# cooler.net
KiCad netlist of a schematic drawn in EAGLE
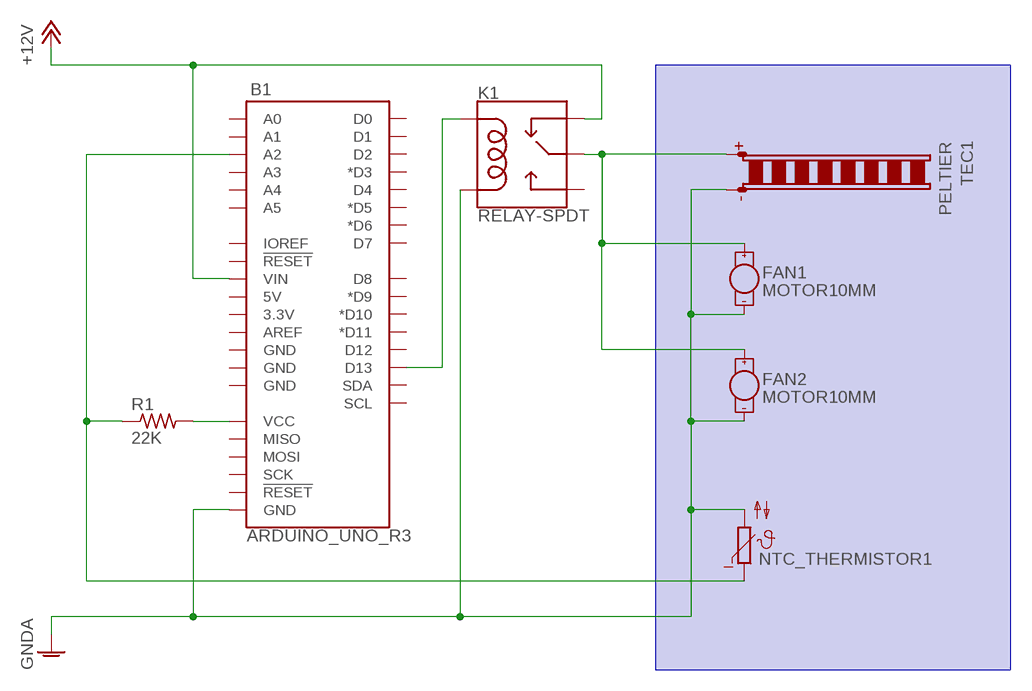
[diagram p0: schematic, sheet 1]

(export (version "E")
  (design (tool "Eeschema 10.0.6"))
  (components
    (comp (ref "B1")
      (value "ARDUINO_UNO_R3")
      (footprint "eagle-import:ARDUINO_R3")
      (libsource (lib "eagle-import") (part "ARDUINO_UNO_R3"))
    )
    (comp (ref "FAN1")
      (value "MOTOR10MM")
      (footprint "eagle-import:VIBE-MOTOR-10MM")
      (libsource (lib "eagle-import") (part "MOTOR10MM"))
    )
    (comp (ref "FAN2")
      (value "MOTOR10MM")
      (footprint "eagle-import:VIBE-MOTOR-10MM")
      (libsource (lib "eagle-import") (part "MOTOR10MM"))
    )
    (comp (ref "K1")
      (value "RELAY-SPDT")
      (footprint "eagle-import:RELAY_G5LE")
      (libsource (lib "eagle-import") (part "RELAY-SPDT"))
    )
    (comp (ref "NTC_THERMISTOR1")
      (value "B57164")
      (footprint "eagle-import:B57164")
      (fields (field (name "MPN") "B57164K474K52"))
      (libsource (lib "eagle-import") (part "B57164"))
    )
    (comp (ref "R1")
      (value "22K")
      (footprint "eagle-import:0204_5")
      (libsource (lib "eagle-import") (part "R-US_0204/5"))
    )
    (comp (ref "TEC1")
      (value "PELTIER")
      (footprint "eagle-import:R_V526-0")
      (libsource (lib "eagle-import") (part "PELTIER"))
    )
  )
  (nets
    (net (code "1") (name "+12V") (class "Default")
      (node (ref "B1") (pin "VIN") (pinfunction "VIN_VIN") (pintype "bidirectional"))
      (node (ref "K1") (pin "4") (pinfunction "NC_4") (pintype "bidirectional"))
    )
    (net (code "2") (name "GNDA") (class "Default")
      (node (ref "B1") (pin "GND@1") (pinfunction "GND_GND@1") (pintype "bidirectional"))
      (node (ref "FAN1") (pin "-") (pinfunction "-_-") (pintype "bidirectional"))
      (node (ref "FAN2") (pin "-") (pinfunction "-_-") (pintype "bidirectional"))
      (node (ref "K1") (pin "5") (pinfunction "COIL2_5") (pintype "bidirectional"))
      (node (ref "NTC_THERMISTOR1") (pin "2") (pinfunction "2_2") (pintype "passive"))
      (node (ref "TEC1") (pin "2") (pinfunction "2_2") (pintype "passive"))
    )
    (net (code "3") (name "Net-(B1-PadA2)") (class "Default")
      (node (ref "B1") (pin "A2") (pinfunction "A2_A2") (pintype "bidirectional"))
      (node (ref "NTC_THERMISTOR1") (pin "1") (pinfunction "1_1") (pintype "passive"))
      (node (ref "R1") (pin "1") (pinfunction "1_1") (pintype "passive"))
    )
    (net (code "4") (name "Net-(B1-PadVCC)") (class "Default")
      (node (ref "B1") (pin "VCC") (pinfunction "VCC_VCC") (pintype "bidirectional"))
      (node (ref "R1") (pin "2") (pinfunction "2_2") (pintype "passive"))
    )
    (net (code "5") (name "Net-(K1-COIL1)") (class "Default")
      (node (ref "B1") (pin "D13") (pinfunction "D13_D13") (pintype "bidirectional"))
      (node (ref "K1") (pin "2") (pinfunction "COIL1_2") (pintype "bidirectional"))
    )
    (net (code "6") (name "Net-(K1-MAIN)") (class "Default")
      (node (ref "FAN1") (pin "+") (pinfunction "+_+") (pintype "bidirectional"))
      (node (ref "FAN2") (pin "+") (pinfunction "+_+") (pintype "bidirectional"))
      (node (ref "K1") (pin "1") (pinfunction "MAIN_1") (pintype "bidirectional"))
      (node (ref "TEC1") (pin "1") (pinfunction "1_1") (pintype "passive"))
    )
    (net (code "7") (name "unconnected-(B1-*D3-PadD3)") (class "Default")
      (node (ref "B1") (pin "D3") (pinfunction "*D3_D3") (pintype "bidirectional"))
    )
    (net (code "8") (name "unconnected-(B1-*D5-PadD5)") (class "Default")
      (node (ref "B1") (pin "D5") (pinfunction "*D5_D5") (pintype "bidirectional"))
    )
    (net (code "9") (name "unconnected-(B1-*D6-PadD6)") (class "Default")
      (node (ref "B1") (pin "D6") (pinfunction "*D6_D6") (pintype "bidirectional"))
    )
    (net (code "10") (name "unconnected-(B1-*D9-PadD9)") (class "Default")
      (node (ref "B1") (pin "D9") (pinfunction "*D9_D9") (pintype "bidirectional"))
    )
    (net (code "11") (name "unconnected-(B1-*D10-PadD10)") (class "Default")
      (node (ref "B1") (pin "D10") (pinfunction "*D10_D10") (pintype "bidirectional"))
    )
    (net (code "12") (name "unconnected-(B1-*D11-PadD11)") (class "Default")
      (node (ref "B1") (pin "D11") (pinfunction "*D11_D11") (pintype "bidirectional"))
    )
    (net (code "13") (name "unconnected-(B1-GND-PadGND@2)") (class "Default")
      (node (ref "B1") (pin "GND@2") (pinfunction "GND_GND@2") (pintype "bidirectional"))
    )
    (net (code "14") (name "unconnected-(B1-GND-PadGND@3)") (class "Default")
      (node (ref "B1") (pin "GND@3") (pinfunction "GND_GND@3") (pintype "bidirectional"))
    )
    (net (code "15") (name "unconnected-(B1-GND-PadGND@4)") (class "Default")
      (node (ref "B1") (pin "GND@4") (pinfunction "GND_GND@4") (pintype "bidirectional"))
    )
    (net (code "16") (name "unconnected-(B1-Pad3.3V)") (class "Default")
      (node (ref "B1") (pin "3.3V") (pinfunction "3.3V_3.3V") (pintype "bidirectional"))
    )
    (net (code "17") (name "unconnected-(B1-Pad5V)") (class "Default")
      (node (ref "B1") (pin "5V") (pinfunction "5V_5V") (pintype "bidirectional"))
    )
    (net (code "18") (name "unconnected-(B1-PadA0)") (class "Default")
      (node (ref "B1") (pin "A0") (pinfunction "A0_A0") (pintype "bidirectional"))
    )
    (net (code "19") (name "unconnected-(B1-PadA1)") (class "Default")
      (node (ref "B1") (pin "A1") (pinfunction "A1_A1") (pintype "bidirectional"))
    )
    (net (code "20") (name "unconnected-(B1-PadA3)") (class "Default")
      (node (ref "B1") (pin "A3") (pinfunction "A3_A3") (pintype "bidirectional"))
    )
    (net (code "21") (name "unconnected-(B1-PadA4)") (class "Default")
      (node (ref "B1") (pin "A4") (pinfunction "A4_A4") (pintype "bidirectional"))
    )
    (net (code "22") (name "unconnected-(B1-PadA5)") (class "Default")
      (node (ref "B1") (pin "A5") (pinfunction "A5_A5") (pintype "bidirectional"))
    )
    (net (code "23") (name "unconnected-(B1-PadAREF)") (class "Default")
      (node (ref "B1") (pin "AREF") (pinfunction "AREF_AREF") (pintype "bidirectional"))
    )
    (net (code "24") (name "unconnected-(B1-PadD0)") (class "Default")
      (node (ref "B1") (pin "D0") (pinfunction "D0_D0") (pintype "bidirectional"))
    )
    (net (code "25") (name "unconnected-(B1-PadD1)") (class "Default")
      (node (ref "B1") (pin "D1") (pinfunction "D1_D1") (pintype "bidirectional"))
    )
    (net (code "26") (name "unconnected-(B1-PadD2)") (class "Default")
      (node (ref "B1") (pin "D2") (pinfunction "D2_D2") (pintype "bidirectional"))
    )
    (net (code "27") (name "unconnected-(B1-PadD4)") (class "Default")
      (node (ref "B1") (pin "D4") (pinfunction "D4_D4") (pintype "bidirectional"))
    )
    (net (code "28") (name "unconnected-(B1-PadD7)") (class "Default")
      (node (ref "B1") (pin "D7") (pinfunction "D7_D7") (pintype "bidirectional"))
    )
    (net (code "29") (name "unconnected-(B1-PadD8)") (class "Default")
      (node (ref "B1") (pin "D8") (pinfunction "D8_D8") (pintype "bidirectional"))
    )
    (net (code "30") (name "unconnected-(B1-PadD12)") (class "Default")
      (node (ref "B1") (pin "D12") (pinfunction "D12_D12") (pintype "bidirectional"))
    )
    (net (code "31") (name "unconnected-(B1-PadIOREF)") (class "Default")
      (node (ref "B1") (pin "IOREF") (pinfunction "IOREF_IOREF") (pintype "bidirectional"))
    )
    (net (code "32") (name "unconnected-(B1-PadMISO)") (class "Default")
      (node (ref "B1") (pin "MISO") (pinfunction "MISO_MISO") (pintype "bidirectional"))
    )
    (net (code "33") (name "unconnected-(B1-PadMOSI)") (class "Default")
      (node (ref "B1") (pin "MOSI") (pinfunction "MOSI_MOSI") (pintype "bidirectional"))
    )
    (net (code "34") (name "unconnected-(B1-PadSCK)") (class "Default")
      (node (ref "B1") (pin "SCK") (pinfunction "SCK_SCK") (pintype "bidirectional"))
    )
    (net (code "35") (name "unconnected-(B1-PadSCL)") (class "Default")
      (node (ref "B1") (pin "SCL") (pinfunction "SCL_SCL") (pintype "bidirectional"))
    )
    (net (code "36") (name "unconnected-(B1-PadSDA)") (class "Default")
      (node (ref "B1") (pin "SDA") (pinfunction "SDA_SDA") (pintype "bidirectional"))
    )
    (net (code "37") (name "unconnected-(B1-~{RESET}-PadRESET@1)") (class "Default")
      (node (ref "B1") (pin "RESET@1") (pinfunction "~{RESET}_RESET@1") (pintype "bidirectional"))
    )
    (net (code "38") (name "unconnected-(B1-~{RESET}-PadRESET@2)") (class "Default")
      (node (ref "B1") (pin "RESET@2") (pinfunction "~{RESET}_RESET@2") (pintype "bidirectional"))
    )
    (net (code "39") (name "unconnected-(K1-NO-Pad3)") (class "Default")
      (node (ref "K1") (pin "3") (pinfunction "NO_3") (pintype "bidirectional"))
    )
  )
)
